# RTD_Channel.net
KiCad netlist of a schematic drawn in Altium Designer
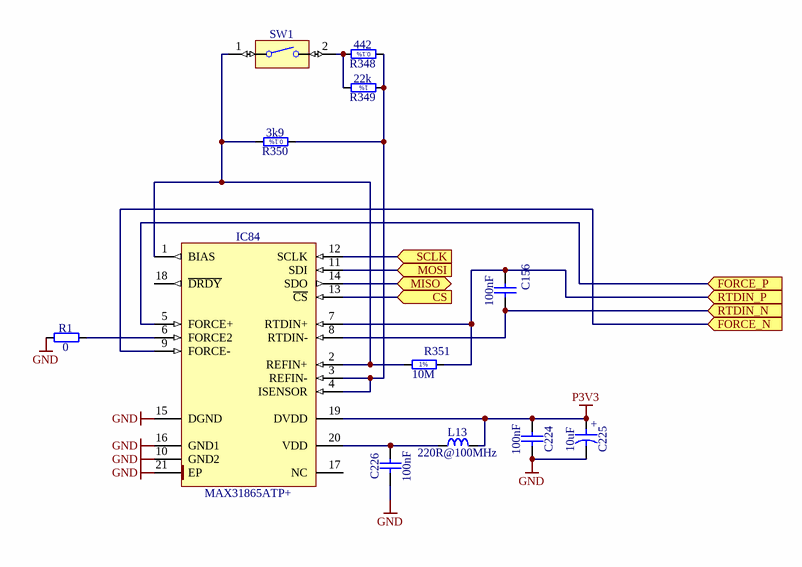
[diagram p0: RTD_Channel.SchDoc]

(export (version "E")
  (design (tool "Eeschema 10.0.6"))
  (components
    (comp (ref "C156")
      (value "100nF")
      (footprint "CAPC1005X55N")
      (description "Non-polarised capacitor")
      (fields
        (field (name "PART NUMBER") "CC0402_100NF_16V_10%_X5R")
        (field (name "VOLTAGE") "16V")
        (field (name "AUTHOR") "CERN DEM JLC")
      )
      (libsource (lib "Capacitors") (part "Capacitor - non polarized"))
    )
    (comp (ref "C224")
      (value "100nF")
      (footprint "CAPC1005X55N")
      (description "Non-polarised capacitor")
      (fields
        (field (name "PART NUMBER") "CC0402_100NF_16V_10%_X5R")
        (field (name "VOLTAGE") "16V")
        (field (name "AUTHOR") "CERN DEM JLC")
      )
      (libsource (lib "Capacitors") (part "Capacitor - non polarized"))
    )
    (comp (ref "C225")
      (value "10uF")
      (footprint "CAPMP3216X180N")
      (description "Polarised capacitor")
      (fields
        (field (name "PART NUMBER") "CTE3216-18_10UF_16V_20%_AVX_TCJ")
        (field (name "VOLTAGE") "16V")
        (field (name "AUTHOR") "CERN DEM JLC")
      )
      (libsource (lib "Capacitors") (part "Capacitor - polarized"))
    )
    (comp (ref "C226")
      (value "100nF")
      (footprint "CAPC1005X55N")
      (description "Non-polarised capacitor")
      (fields
        (field (name "PART NUMBER") "CC0402_100NF_16V_10%_X5R")
        (field (name "VOLTAGE") "16V")
        (field (name "AUTHOR") "CERN DEM JLC")
      )
      (libsource (lib "Capacitors") (part "Capacitor - non polarized"))
    )
    (comp (ref "IC84")
      (value "MAX31865ATP+")
      (footprint "QFN65P500X500X80-21N-S335")
      (description "RTD-to-Digital Converter")
      (fields (field (name "MANUFACTURER") "MAXIM") (field (name "AUTHOR") "CERN DEM MR"))
      (libsource (lib "ICs And Semiconductors") (part "MAX31865ATP+"))
    )
    (comp (ref "L13")
      (value "220R@100MHz")
      (footprint "INDC1005X55N")
      (description "Inductor")
      (fields
        (field (name "PART NUMBER") "IND0402_MURATA_BLM15HB221SN1")
        (field (name "POWER") "250mA")
        (field (name "AUTHOR") "CERN DEM JLC")
      )
      (libsource (lib "Inductors & Transformers") (part "Inductor"))
    )
    (comp (ref "R1")
      (value "0")
      (footprint "RESC1005X40N")
      (description "Resistor")
      (fields
        (field (name "PART NUMBER") "R0402_0R_JUMPER")
        (field (name "MANUFACTURER") "GENERIC")
        (field (name "AUTHOR") "CERN DEM JLC")
      )
      (libsource (lib "Resistors") (part "Resistor"))
    )
    (comp (ref "R348")
      (value "442")
      (footprint "RESC1608X55N")
      (description "Resistor - 0.1%")
      (fields
        (field (name "PART NUMBER") "R0603_442R_0.1%_0.063W_25PPM")
        (field (name "POWER") "0.063W")
        (field (name "AUTHOR") "GK")
      )
      (libsource (lib "LIBRARY_SCH") (part "RES_0603_442R_0.1%_25ppm"))
    )
    (comp (ref "R349")
      (value "22k")
      (footprint "RESC1005X40N")
      (description "Resistor - 1%")
      (fields
        (field (name "PART NUMBER") "R0402_22K_1%_0.0625W_100PPM")
        (field (name "POWER") "0.0625W")
        (field (name "AUTHOR") "CERN DEM JLC")
      )
      (libsource (lib "Resistors") (part "Resistor - 1%"))
    )
    (comp (ref "R350")
      (value "3k9")
      (footprint "RESC1608X55N")
      (description "Resistor - 0.1%")
      (fields
        (field (name "PART NUMBER") "R0603_3k9_0.1%_0.063W_10PPM")
        (field (name "POWER") "0.063W")
        (field (name "AUTHOR") "GK")
      )
      (libsource (lib "LIBRARY_SCH") (part "RES_0603_3k9_0.1%_10ppm"))
    )
    (comp (ref "R351")
      (value "10M")
      (footprint "RESC1608X55N")
      (description "Resistor - 1%")
      (fields
        (field (name "PART NUMBER") "R0603_10M_1%_0.1W_100PPM")
        (field (name "POWER") "0.1W")
        (field (name "AUTHOR") "CERN DEM JLC")
      )
      (libsource (lib "Resistors") (part "Resistor - 1%"))
    )
    (comp (ref "SW1")
      (value "Switch")
      (footprint "SW_OMRON_A6SN-1101")
      (description "1 Ways SPST DIP Switch")
      (fields
        (field (name "PART NUMBER") "SW_OMRON_A6SN-1101")
        (field (name "MANUFACTURER") "OMRON")
        (field (name "AUTHOR") "CERN DEM JLC")
      )
      (libsource (lib "Eletro-mechanical") (part "SW 1x SPST DIP Switch"))
    )
  )
  (nets
    (net (code "1") (name "/CS") (class "Default")
      (node (ref "IC84") (pin "13") (pinfunction "~{CS}_13") (pintype "input"))
    )
    (net (code "2") (name "/FORCE_N") (class "Default")
      (node (ref "IC84") (pin "9") (pinfunction "FORCE-_9") (pintype "input"))
    )
    (net (code "3") (name "/FORCE_P") (class "Default")
      (node (ref "IC84") (pin "5") (pinfunction "FORCE+_5") (pintype "input"))
    )
    (net (code "4") (name "/MISO") (class "Default")
      (node (ref "IC84") (pin "14") (pinfunction "SDO_14") (pintype "output"))
    )
    (net (code "5") (name "/MOSI") (class "Default")
      (node (ref "IC84") (pin "11") (pinfunction "SDI_11") (pintype "input"))
    )
    (net (code "6") (name "/RTDIN_N") (class "Default")
      (node (ref "C156") (pin "2") (pinfunction "2_2") (pintype "passive"))
      (node (ref "IC84") (pin "8") (pinfunction "RTDIN-_8") (pintype "input"))
    )
    (net (code "7") (name "/RTDIN_P") (class "Default")
      (node (ref "C156") (pin "1") (pinfunction "1_1") (pintype "passive"))
      (node (ref "IC84") (pin "7") (pinfunction "RTDIN+_7") (pintype "input"))
      (node (ref "R351") (pin "2") (pinfunction "2_2") (pintype "passive"))
    )
    (net (code "8") (name "/SCLK") (class "Default")
      (node (ref "IC84") (pin "12") (pinfunction "SCLK_12") (pintype "input"))
    )
    (net (code "9") (name "GND") (class "Default")
      (node (ref "C224") (pin "2") (pinfunction "2_2") (pintype "passive"))
      (node (ref "C225") (pin "2") (pinfunction "2_2") (pintype "passive"))
      (node (ref "C226") (pin "1") (pinfunction "1_1") (pintype "passive"))
      (node (ref "IC84") (pin "10") (pinfunction "GND2_10") (pintype "power_in"))
      (node (ref "IC84") (pin "15") (pinfunction "DGND_15") (pintype "power_in"))
      (node (ref "IC84") (pin "16") (pinfunction "GND1_16") (pintype "power_in"))
      (node (ref "IC84") (pin "21") (pinfunction "EP_21") (pintype "power_in"))
      (node (ref "R1") (pin "1") (pinfunction "1_1") (pintype "passive"))
    )
    (net (code "10") (name "Net-(IC84-BIAS)") (class "Default")
      (node (ref "IC84") (pin "1") (pinfunction "BIAS_1") (pintype "output"))
      (node (ref "IC84") (pin "2") (pinfunction "REFIN+_2") (pintype "input"))
      (node (ref "R350") (pin "2") (pinfunction "2_2") (pintype "passive"))
      (node (ref "R351") (pin "1") (pinfunction "1_1") (pintype "passive"))
      (node (ref "SW1") (pin "1") (pinfunction "1_1") (pintype "bidirectional"))
    )
    (net (code "11") (name "Net-(IC84-FORCE2)") (class "Default")
      (node (ref "IC84") (pin "6") (pinfunction "FORCE2_6") (pintype "input"))
      (node (ref "R1") (pin "2") (pinfunction "2_2") (pintype "passive"))
    )
    (net (code "12") (name "Net-(IC84-ISENSOR)") (class "Default")
      (node (ref "IC84") (pin "3") (pinfunction "REFIN-_3") (pintype "input"))
      (node (ref "IC84") (pin "4") (pinfunction "ISENSOR_4") (pintype "input"))
      (node (ref "R348") (pin "1") (pinfunction "1_1") (pintype "passive"))
      (node (ref "R349") (pin "1") (pinfunction "1_1") (pintype "passive"))
      (node (ref "R350") (pin "1") (pinfunction "1_1") (pintype "passive"))
    )
    (net (code "13") (name "Net-(IC84-VDD)") (class "Default")
      (node (ref "C226") (pin "2") (pinfunction "2_2") (pintype "passive"))
      (node (ref "IC84") (pin "20") (pinfunction "VDD_20") (pintype "power_in"))
      (node (ref "L13") (pin "1") (pinfunction "1_1") (pintype "passive"))
    )
    (net (code "14") (name "Net-(R348-Pad2)") (class "Default")
      (node (ref "R348") (pin "2") (pinfunction "2_2") (pintype "passive"))
      (node (ref "R349") (pin "2") (pinfunction "2_2") (pintype "passive"))
      (node (ref "SW1") (pin "2") (pinfunction "2_2") (pintype "bidirectional"))
    )
    (net (code "15") (name "P3V3") (class "Default")
      (node (ref "C224") (pin "1") (pinfunction "1_1") (pintype "passive"))
      (node (ref "C225") (pin "1") (pinfunction "1_1") (pintype "passive"))
      (node (ref "IC84") (pin "19") (pinfunction "DVDD_19") (pintype "power_in"))
      (node (ref "L13") (pin "2") (pinfunction "2_2") (pintype "passive"))
    )
    (net (code "16") (name "unconnected-(IC84-NC-Pad17)") (class "Default")
      (node (ref "IC84") (pin "17") (pinfunction "NC_17") (pintype "passive"))
    )
    (net (code "17") (name "unconnected-(IC84-~{DRDY}-Pad18)") (class "Default")
      (node (ref "IC84") (pin "18") (pinfunction "~{DRDY}_18") (pintype "output"))
    )
  )
)
